# Sheet1.net
KiCad netlist of a schematic drawn in Altium Designer
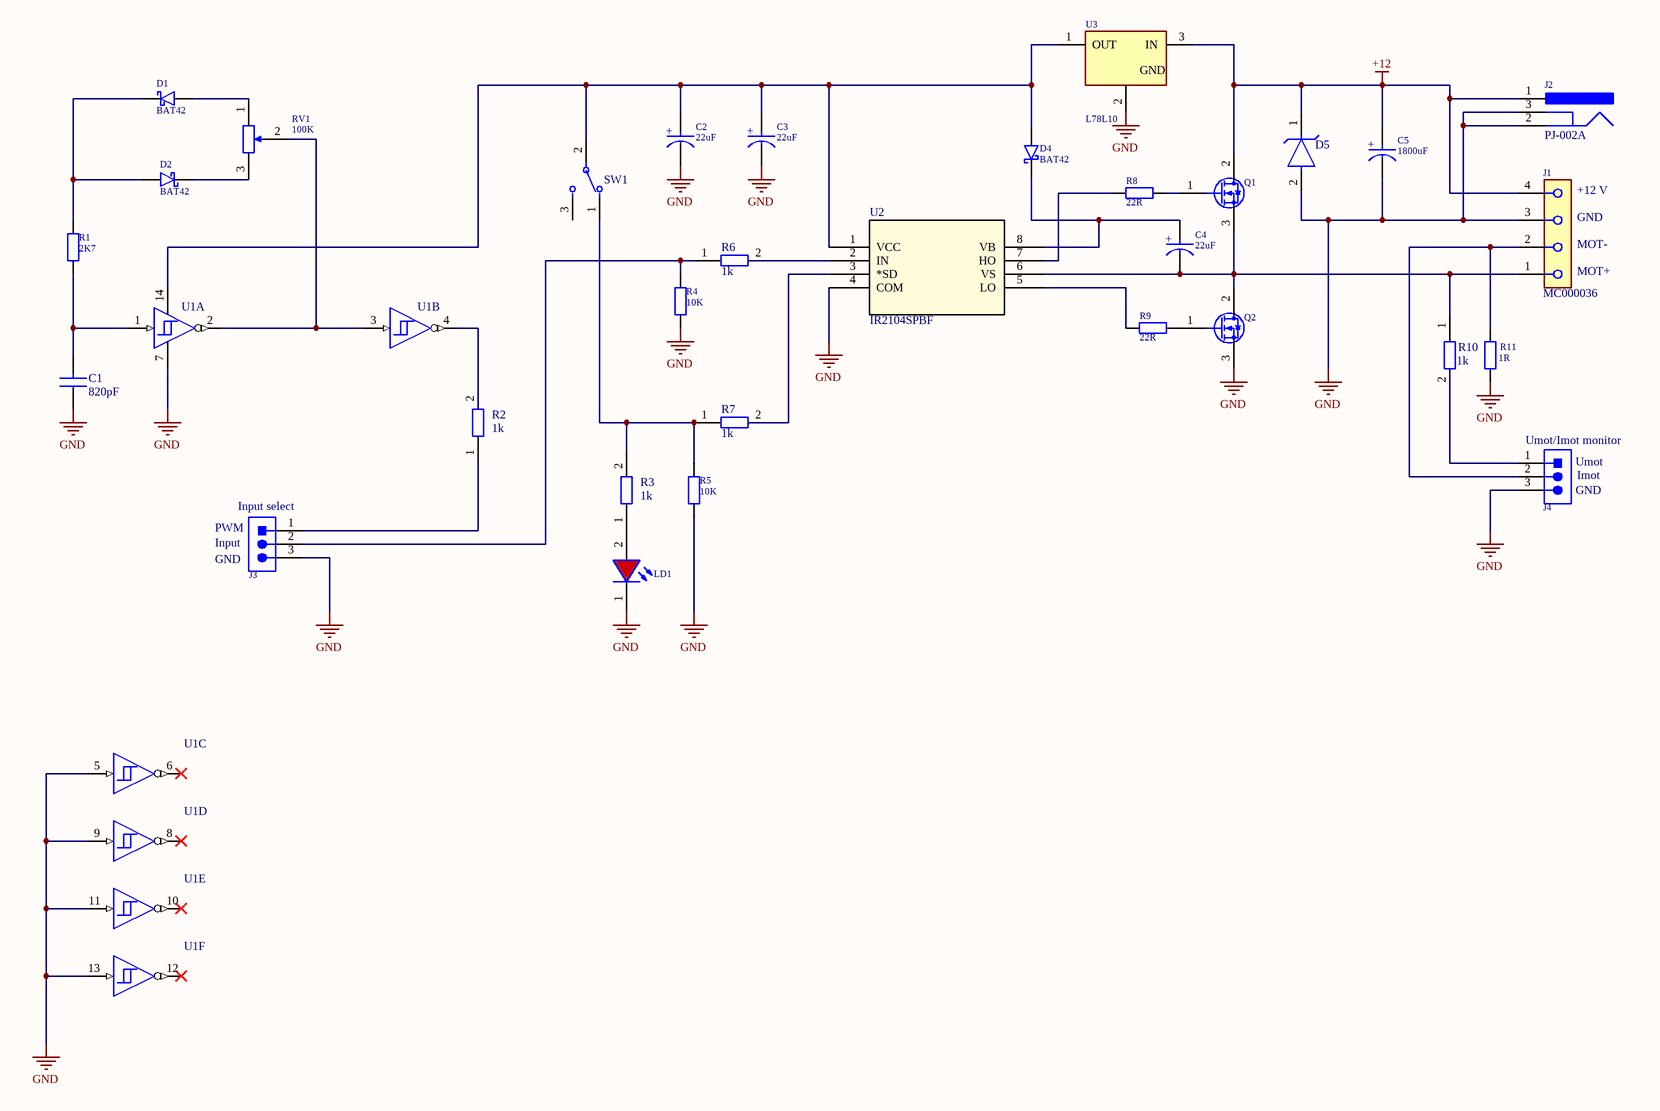
[diagram p0: Sheet1.SchDoc]

(export (version "E")
  (design (tool "Eeschema 10.0.6"))
  (components
    (comp (ref "C1")
      (value "820pF")
      (footprint "DC_motor_lib:Cap_tht_5mm")
      (description "Ceramic Disc Capacitor, 820 pF, 100 V, ± 10%, Y5P, 5 mm, Radial Leaded")
      (fields (field (name "CAPACITANCE") "820pF"))
      (libsource (lib "DC_motor_lib") (part "Capacitor 820pF"))
    )
    (comp (ref "C2")
      (value "ECA1EM220I")
      (footprint "DC_motor_lib:Cap_radial_5mm")
      (description "Electrolytic Capacitor, 22 µF, 25 V, ± 20%, Radial Leaded, 2000 hours @ 85°C, Polar")
      (fields (field (name "CAPACITANCE") "22uF"))
      (libsource (lib "DC_motor_lib") (part "Capacitor Electrolytic 5mm"))
    )
    (comp (ref "C3")
      (value "ECA1EM220I")
      (footprint "DC_motor_lib:Cap_radial_5mm")
      (description "Electrolytic Capacitor, 22 µF, 25 V, ± 20%, Radial Leaded, 2000 hours @ 85°C, Polar")
      (fields (field (name "CAPACITANCE") "22uF"))
      (libsource (lib "DC_motor_lib") (part "Capacitor Electrolytic 5mm"))
    )
    (comp (ref "C4")
      (value "ECA1EM220I")
      (footprint "DC_motor_lib:Cap_radial_5mm")
      (description "Electrolytic Capacitor, 22 µF, 25 V, ± 20%, Radial Leaded, 2000 hours @ 85°C, Polar")
      (fields (field (name "CAPACITANCE") "22uF"))
      (libsource (lib "DC_motor_lib") (part "Capacitor Electrolytic 5mm"))
    )
    (comp (ref "C5")
      (value "B41896D5188M000")
      (footprint "DC_motor_lib:Cap_Radial_16mm")
      (description "Electrolytic Capacitor, 1800 µF, 25 V, ± 20%, Radial Leaded, 7000 hours @ 125°C, Polar")
      (fields (field (name "CAPACITANCE") "1800uF"))
      (libsource (lib "DC_motor_lib") (part "Capacitor Electrolytic 16mm"))
    )
    (comp (ref "D1")
      (value "BAT42")
      (footprint "DC_motor_lib:BAT42")
      (description "Small Signal Schottky Diode, Single, 30 V, 200 mA, 400 mV, 4 A, 125 °C")
      (libsource (lib "DC_motor_lib") (part "Schottky diode 30 V"))
    )
    (comp (ref "D2")
      (value "BAT42")
      (footprint "DC_motor_lib:BAT42")
      (description "Small Signal Schottky Diode, Single, 30 V, 200 mA, 400 mV, 4 A, 125 °C")
      (libsource (lib "DC_motor_lib") (part "Schottky diode 30 V"))
    )
    (comp (ref "D4")
      (value "BAT42")
      (footprint "DC_motor_lib:BAT42")
      (description "Small Signal Schottky Diode, Single, 30 V, 200 mA, 400 mV, 4 A, 125 °C")
      (libsource (lib "DC_motor_lib") (part "Schottky diode 30 V"))
    )
    (comp (ref "D5")
      (value "1N4749ATR")
      (footprint "DC_motor_lib:FP-017AH-MFG")
      (description "1N4749ATR 1N4749 Series 24 V 1 W 5 uA Through Hole Zener Diode - DO-41")
      (fields (field (name "TOLERANCE") "5%"))
      (libsource (lib "DC_motor_lib") (part "zener_diode24V"))
    )
    (comp (ref "J1")
      (value "MC000036")
      (footprint "DC_motor_lib:MC000036")
      (description "MULTICOMP PRO MC000036Wire-To-Board Terminal Block, 5.08 mm, 4 Ways, 26 AWG, 12 AWG, 4 mm², Screw")
      (libsource (lib "DC_motor_lib") (part "Screw terminal"))
    )
    (comp (ref "J2")
      (value "PJ-002A")
      (footprint "DC_motor_lib:DC_jack")
      (fields (field (name "MANUFACTURER") "CUIInc."))
      (libsource (lib "DC_motor_lib") (part "Power Jack"))
    )
    (comp (ref "J3")
      (value "5-146278-3")
      (footprint "DC_motor_lib:TE_5-146278-3")
      (description "Pin Header, Board-to-Board, 2.54 mm, 1 Rows, 3 Contacts, Through Hole Straight, AMPMODU II Series")
      (libsource (lib "") (part "Header 3x1M_1"))
    )
    (comp (ref "J4")
      (value "5-146278-3")
      (footprint "DC_motor_lib:TE_5-146278-3")
      (description "Pin Header, Board-to-Board, 2.54 mm, 1 Rows, 3 Contacts, Through Hole Straight, AMPMODU II Series")
      (libsource (lib "DC_motor_lib") (part "Header 3x1M"))
    )
    (comp (ref "LD1")
      (value "TLHR5200")
      (footprint "DC_motor_lib:LED_5.0mm")
      (description "LED, Red, Through Hole, T-1 3/4 (5mm), 20 mA, 2 V, 635 nm")
      (libsource (lib "DC_motor_lib") (part "LED Red"))
    )
    (comp (ref "Q1")
      (value "IRFU3910PBF")
      (footprint "DC_motor_lib:TO-251AA")
      (description "Power MOSFET, N Channel, 100 V, 16 A, 0.115 ohm, TO-251AA, Through Hole")
      (libsource (lib "DC_motor_lib") (part "MOSFET N-channel 16A"))
    )
    (comp (ref "Q2")
      (value "IRFU3910PBF")
      (footprint "DC_motor_lib:TO-251AA")
      (description "Power MOSFET, N Channel, 100 V, 16 A, 0.115 ohm, TO-251AA, Through Hole")
      (libsource (lib "DC_motor_lib") (part "MOSFET N-channel 16A"))
    )
    (comp (ref "R1")
      (value "2K7")
      (footprint "DC_motor_lib:Res_2k7_Axial_DIN0207")
      (libsource (lib "DC_motor_lib") (part "Res_2k7"))
    )
    (comp (ref "R2") (value "1k") (footprint "DC_motor_lib:resistor_1k") (libsource (lib "") (part "R1k_2")))
    (comp (ref "R3") (value "1k") (footprint "DC_motor_lib:resistor_1k") (libsource (lib "") (part "R1k_2")))
    (comp (ref "R4")
      (value "10K")
      (footprint "DC_motor_lib:Res_10k_Axial_DIN0207")
      (libsource (lib "DC_motor_lib") (part "Res_10k"))
    )
    (comp (ref "R5")
      (value "10K")
      (footprint "DC_motor_lib:Res_10k_Axial_DIN0207")
      (libsource (lib "DC_motor_lib") (part "Res_10k"))
    )
    (comp (ref "R6")
      (value "1k")
      (footprint "DC_motor_lib:resistor_1k")
      (libsource (lib "DC_motor_lib") (part "R1k"))
    )
    (comp (ref "R7")
      (value "1k")
      (footprint "DC_motor_lib:resistor_1k")
      (libsource (lib "DC_motor_lib") (part "R1k"))
    )
    (comp (ref "R8")
      (value "22R")
      (footprint "DC_motor_lib:Res_22R_Axial_DIN0207")
      (libsource (lib "DC_motor_lib") (part "Res_22R"))
    )
    (comp (ref "R9")
      (value "22R")
      (footprint "DC_motor_lib:Res_22R_Axial_DIN0207")
      (libsource (lib "DC_motor_lib") (part "Res_22R"))
    )
    (comp (ref "R10") (value "1k") (footprint "DC_motor_lib:resistor_1k") (libsource (lib "") (part "R1k_1")))
    (comp (ref "R11")
      (value "1R")
      (footprint "DC_motor_lib:Res_1R_Axial_DIN0309")
      (fields (field (name "Comment") "1R / 0.5W"))
      (libsource (lib "DC_motor_lib") (part "Res_1R"))
    )
    (comp (ref "RV1")
      (value "100K")
      (footprint "DC_motor_lib:Potentiometer")
      (fields (field (name "Comment") "14TR08SA104C"))
      (libsource (lib "DC_motor_lib") (part "Trimmer"))
    )
    (comp (ref "SW1")
      (value "A201SYCB04")
      (footprint "DC_motor_lib:A201SYCB04")
      (description "Toggle Switch, On-On, DPDT, Non Illuminated, GEMINI, Panel Mount")
      (libsource (lib "DC_motor_lib") (part "Toggle Switch"))
    )
    (comp (ref "U1")
      (value "CD40106BE")
      (footprint "DC_motor_lib:DIP762W45P254L1969H508Q14")
      (description "Logic IC, Inverter, Hex, 1 Inputs, 14 Pins, DIP, 40106")
      (libsource (lib "DC_motor_lib") (part "Schmitt trigger"))
    )
    (comp (ref "U2")
      (value "IR2104SPBF")
      (footprint "DC_motor_lib:SOIC8_INF-M")
      (description "No Description Available")
      (libsource (lib "DC_motor_lib") (part "IR2104SPBF"))
    )
    (comp (ref "U3")
      (value "L78L10")
      (footprint "DC_motor_lib:TO-92")
      (description "Linear Voltage Regulator, Fixed, 16V to 35V Input, 10V/100mA Out, TO-92")
      (libsource (lib "DC_motor_lib") (part "LDO 10V"))
    )
  )
  (nets
    (net (code "1") (name "+12") (class "Default")
      (node (ref "C5") (pin "2") (pinfunction "A_2") (pintype "passive"))
      (node (ref "D5") (pin "1") (pinfunction "C_1") (pintype "passive"))
      (node (ref "J1") (pin "4") (pinfunction "4_4") (pintype "passive"))
      (node (ref "J2") (pin "1") (pinfunction "1_1") (pintype "passive"))
      (node (ref "Q1") (pin "2") (pinfunction "2_2") (pintype "passive"))
      (node (ref "U3") (pin "3") (pinfunction "IN_3") (pintype "power_in"))
    )
    (net (code "2") (name "GND") (class "Default")
      (node (ref "C1") (pin "2") (pinfunction "2_2") (pintype "passive"))
      (node (ref "C2") (pin "1") (pinfunction "C_1") (pintype "passive"))
      (node (ref "C3") (pin "1") (pinfunction "C_1") (pintype "passive"))
      (node (ref "C5") (pin "1") (pinfunction "C_1") (pintype "passive"))
      (node (ref "D5") (pin "2") (pinfunction "A_2") (pintype "passive"))
      (node (ref "J1") (pin "3") (pinfunction "3_3") (pintype "passive"))
      (node (ref "J2") (pin "2") (pinfunction "2_2") (pintype "passive"))
      (node (ref "J2") (pin "3") (pinfunction "3_3") (pintype "passive"))
      (node (ref "J3") (pin "3") (pinfunction "3_3") (pintype "passive"))
      (node (ref "J4") (pin "3") (pinfunction "3_3") (pintype "passive"))
      (node (ref "LD1") (pin "1") (pinfunction "K_1") (pintype "passive"))
      (node (ref "Q2") (pin "3") (pinfunction "3_3") (pintype "passive"))
      (node (ref "R11") (pin "2") (pinfunction "2_2") (pintype "passive"))
      (node (ref "R4") (pin "2") (pinfunction "2_2") (pintype "passive"))
      (node (ref "R5") (pin "2") (pinfunction "2_2") (pintype "passive"))
      (node (ref "U1") (pin "11") (pinfunction "E_11") (pintype "input"))
      (node (ref "U1") (pin "13") (pinfunction "F_13") (pintype "input"))
      (node (ref "U1") (pin "5") (pinfunction "C_5") (pintype "input"))
      (node (ref "U1") (pin "7") (pinfunction "VSS_7") (pintype "power_in"))
      (node (ref "U1") (pin "9") (pinfunction "D_9") (pintype "input"))
      (node (ref "U2") (pin "4") (pinfunction "COM_4") (pintype "passive"))
      (node (ref "U3") (pin "2") (pinfunction "ADJ/GND_2") (pintype "passive"))
    )
    (net (code "3") (name "Net-(C2-A)") (class "Default")
      (node (ref "C2") (pin "2") (pinfunction "A_2") (pintype "passive"))
      (node (ref "C3") (pin "2") (pinfunction "A_2") (pintype "passive"))
      (node (ref "D4") (pin "2") (pinfunction "A_2") (pintype "passive"))
      (node (ref "SW1") (pin "2") (pinfunction "2_2") (pintype "passive"))
      (node (ref "U1") (pin "14") (pinfunction "VDD_14") (pintype "power_in"))
      (node (ref "U2") (pin "1") (pinfunction "VCC_1") (pintype "power_in"))
      (node (ref "U3") (pin "1") (pinfunction "OUT_1") (pintype "power_in"))
    )
    (net (code "4") (name "Net-(C4-A)") (class "Default")
      (node (ref "C4") (pin "2") (pinfunction "A_2") (pintype "passive"))
      (node (ref "D4") (pin "1") (pinfunction "K_1") (pintype "passive"))
      (node (ref "U2") (pin "8") (pinfunction "VB_8") (pintype "passive"))
    )
    (net (code "5") (name "Net-(C4-C)") (class "Default")
      (node (ref "C4") (pin "1") (pinfunction "C_1") (pintype "passive"))
      (node (ref "J1") (pin "1") (pinfunction "1_1") (pintype "passive"))
      (node (ref "Q1") (pin "3") (pinfunction "3_3") (pintype "passive"))
      (node (ref "Q2") (pin "2") (pinfunction "2_2") (pintype "passive"))
      (node (ref "R10") (pin "1") (pintype "passive"))
      (node (ref "U2") (pin "6") (pinfunction "VS_6") (pintype "passive"))
    )
    (net (code "6") (name "Net-(D1-A)") (class "Default")
      (node (ref "D1") (pin "2") (pinfunction "A_2") (pintype "passive"))
      (node (ref "RV1") (pin "1") (pinfunction "1_1") (pintype "passive"))
    )
    (net (code "7") (name "Net-(D1-K)") (class "Default")
      (node (ref "D1") (pin "1") (pinfunction "K_1") (pintype "passive"))
      (node (ref "D2") (pin "2") (pinfunction "A_2") (pintype "passive"))
      (node (ref "R1") (pin "1") (pinfunction "1_1") (pintype "passive"))
    )
    (net (code "8") (name "Net-(D2-K)") (class "Default")
      (node (ref "D2") (pin "1") (pinfunction "K_1") (pintype "passive"))
      (node (ref "RV1") (pin "3") (pinfunction "3_3") (pintype "passive"))
    )
    (net (code "9") (name "Net-(J1-Pad2)") (class "Default")
      (node (ref "J1") (pin "2") (pinfunction "2_2") (pintype "passive"))
      (node (ref "J4") (pin "2") (pinfunction "2_2") (pintype "passive"))
      (node (ref "R11") (pin "1") (pinfunction "1_1") (pintype "passive"))
    )
    (net (code "10") (name "Net-(J3-Pad1)") (class "Default")
      (node (ref "J3") (pin "1") (pinfunction "1_1") (pintype "passive"))
      (node (ref "R2") (pin "1") (pintype "passive"))
    )
    (net (code "11") (name "Net-(J3-Pad2)") (class "Default")
      (node (ref "J3") (pin "2") (pinfunction "2_2") (pintype "passive"))
      (node (ref "R4") (pin "1") (pinfunction "1_1") (pintype "passive"))
      (node (ref "R6") (pin "1") (pintype "passive"))
    )
    (net (code "12") (name "Net-(J4-Pad1)") (class "Default")
      (node (ref "J4") (pin "1") (pinfunction "1_1") (pintype "passive"))
      (node (ref "R10") (pin "2") (pintype "passive"))
    )
    (net (code "13") (name "Net-(LD1-A)") (class "Default")
      (node (ref "LD1") (pin "2") (pinfunction "A_2") (pintype "passive"))
      (node (ref "R3") (pin "1") (pintype "passive"))
    )
    (net (code "14") (name "Net-(Q1-Pad1)") (class "Default")
      (node (ref "Q1") (pin "1") (pinfunction "1_1") (pintype "passive"))
      (node (ref "R8") (pin "2") (pinfunction "2_2") (pintype "passive"))
    )
    (net (code "15") (name "Net-(Q2-Pad1)") (class "Default")
      (node (ref "Q2") (pin "1") (pinfunction "1_1") (pintype "passive"))
      (node (ref "R9") (pin "2") (pinfunction "2_2") (pintype "passive"))
    )
    (net (code "16") (name "Net-(R5-Pad1)") (class "Default")
      (node (ref "R5") (pin "1") (pinfunction "1_1") (pintype "passive"))
      (node (ref "R7") (pin "1") (pintype "passive"))
      (node (ref "SW1") (pin "1") (pinfunction "1_1") (pintype "passive"))
    )
    (net (code "17") (name "Net-(U1A-A)") (class "Default")
      (node (ref "C1") (pin "1") (pinfunction "1_1") (pintype "passive"))
      (node (ref "R1") (pin "2") (pinfunction "2_2") (pintype "passive"))
      (node (ref "U1") (pin "1") (pinfunction "A_1") (pintype "input"))
    )
    (net (code "18") (name "Net-(U1A-G=~{A})") (class "Default")
      (node (ref "RV1") (pin "2") (pinfunction "2_2") (pintype "passive"))
      (node (ref "U1") (pin "2") (pinfunction "G=~{A}_2") (pintype "output"))
      (node (ref "U1") (pin "3") (pinfunction "B_3") (pintype "input"))
    )
    (net (code "19") (name "Net-(U1B-H=~{B})") (class "Default")
      (node (ref "R2") (pin "2") (pintype "passive"))
      (node (ref "U1") (pin "4") (pinfunction "H=~{B}_4") (pintype "output"))
    )
    (net (code "20") (name "Net-(U2-*SD)") (class "Default")
      (node (ref "R7") (pin "2") (pintype "passive"))
      (node (ref "U2") (pin "3") (pinfunction "*SD_3") (pintype "passive"))
    )
    (net (code "21") (name "Net-(U2-HO)") (class "Default")
      (node (ref "R8") (pin "1") (pinfunction "1_1") (pintype "passive"))
      (node (ref "U2") (pin "7") (pinfunction "HO_7") (pintype "passive"))
    )
    (net (code "22") (name "Net-(U2-IN)") (class "Default")
      (node (ref "R6") (pin "2") (pintype "passive"))
      (node (ref "U2") (pin "2") (pinfunction "IN_2") (pintype "passive"))
    )
    (net (code "23") (name "Net-(U2-LO)") (class "Default")
      (node (ref "R9") (pin "1") (pinfunction "1_1") (pintype "passive"))
      (node (ref "U2") (pin "5") (pinfunction "LO_5") (pintype "passive"))
    )
    (net (code "24") (name "unconnected-(R3-Pad2)") (class "Default")
      (node (ref "R3") (pin "2") (pintype "passive"))
    )
    (net (code "25") (name "unconnected-(SW1-Pad3)") (class "Default")
      (node (ref "SW1") (pin "3") (pinfunction "3_3") (pintype "passive"))
    )
    (net (code "26") (name "unconnected-(U1C-I=~{C}-Pad6)") (class "Default")
      (node (ref "U1") (pin "6") (pinfunction "I=~{C}_6") (pintype "output+no_connect"))
    )
    (net (code "27") (name "unconnected-(U1D-J=~{D}-Pad8)") (class "Default")
      (node (ref "U1") (pin "8") (pinfunction "J=~{D}_8") (pintype "output+no_connect"))
    )
    (net (code "28") (name "unconnected-(U1E-K=~{E}-Pad10)") (class "Default")
      (node (ref "U1") (pin "10") (pinfunction "K=~{E}_10") (pintype "output+no_connect"))
    )
    (net (code "29") (name "unconnected-(U1F-L=~{F}-Pad12)") (class "Default")
      (node (ref "U1") (pin "12") (pinfunction "L=~{F}_12") (pintype "output+no_connect"))
    )
  )
)
